# Sheet1.net
KiCad netlist of a schematic drawn in Altium Designer
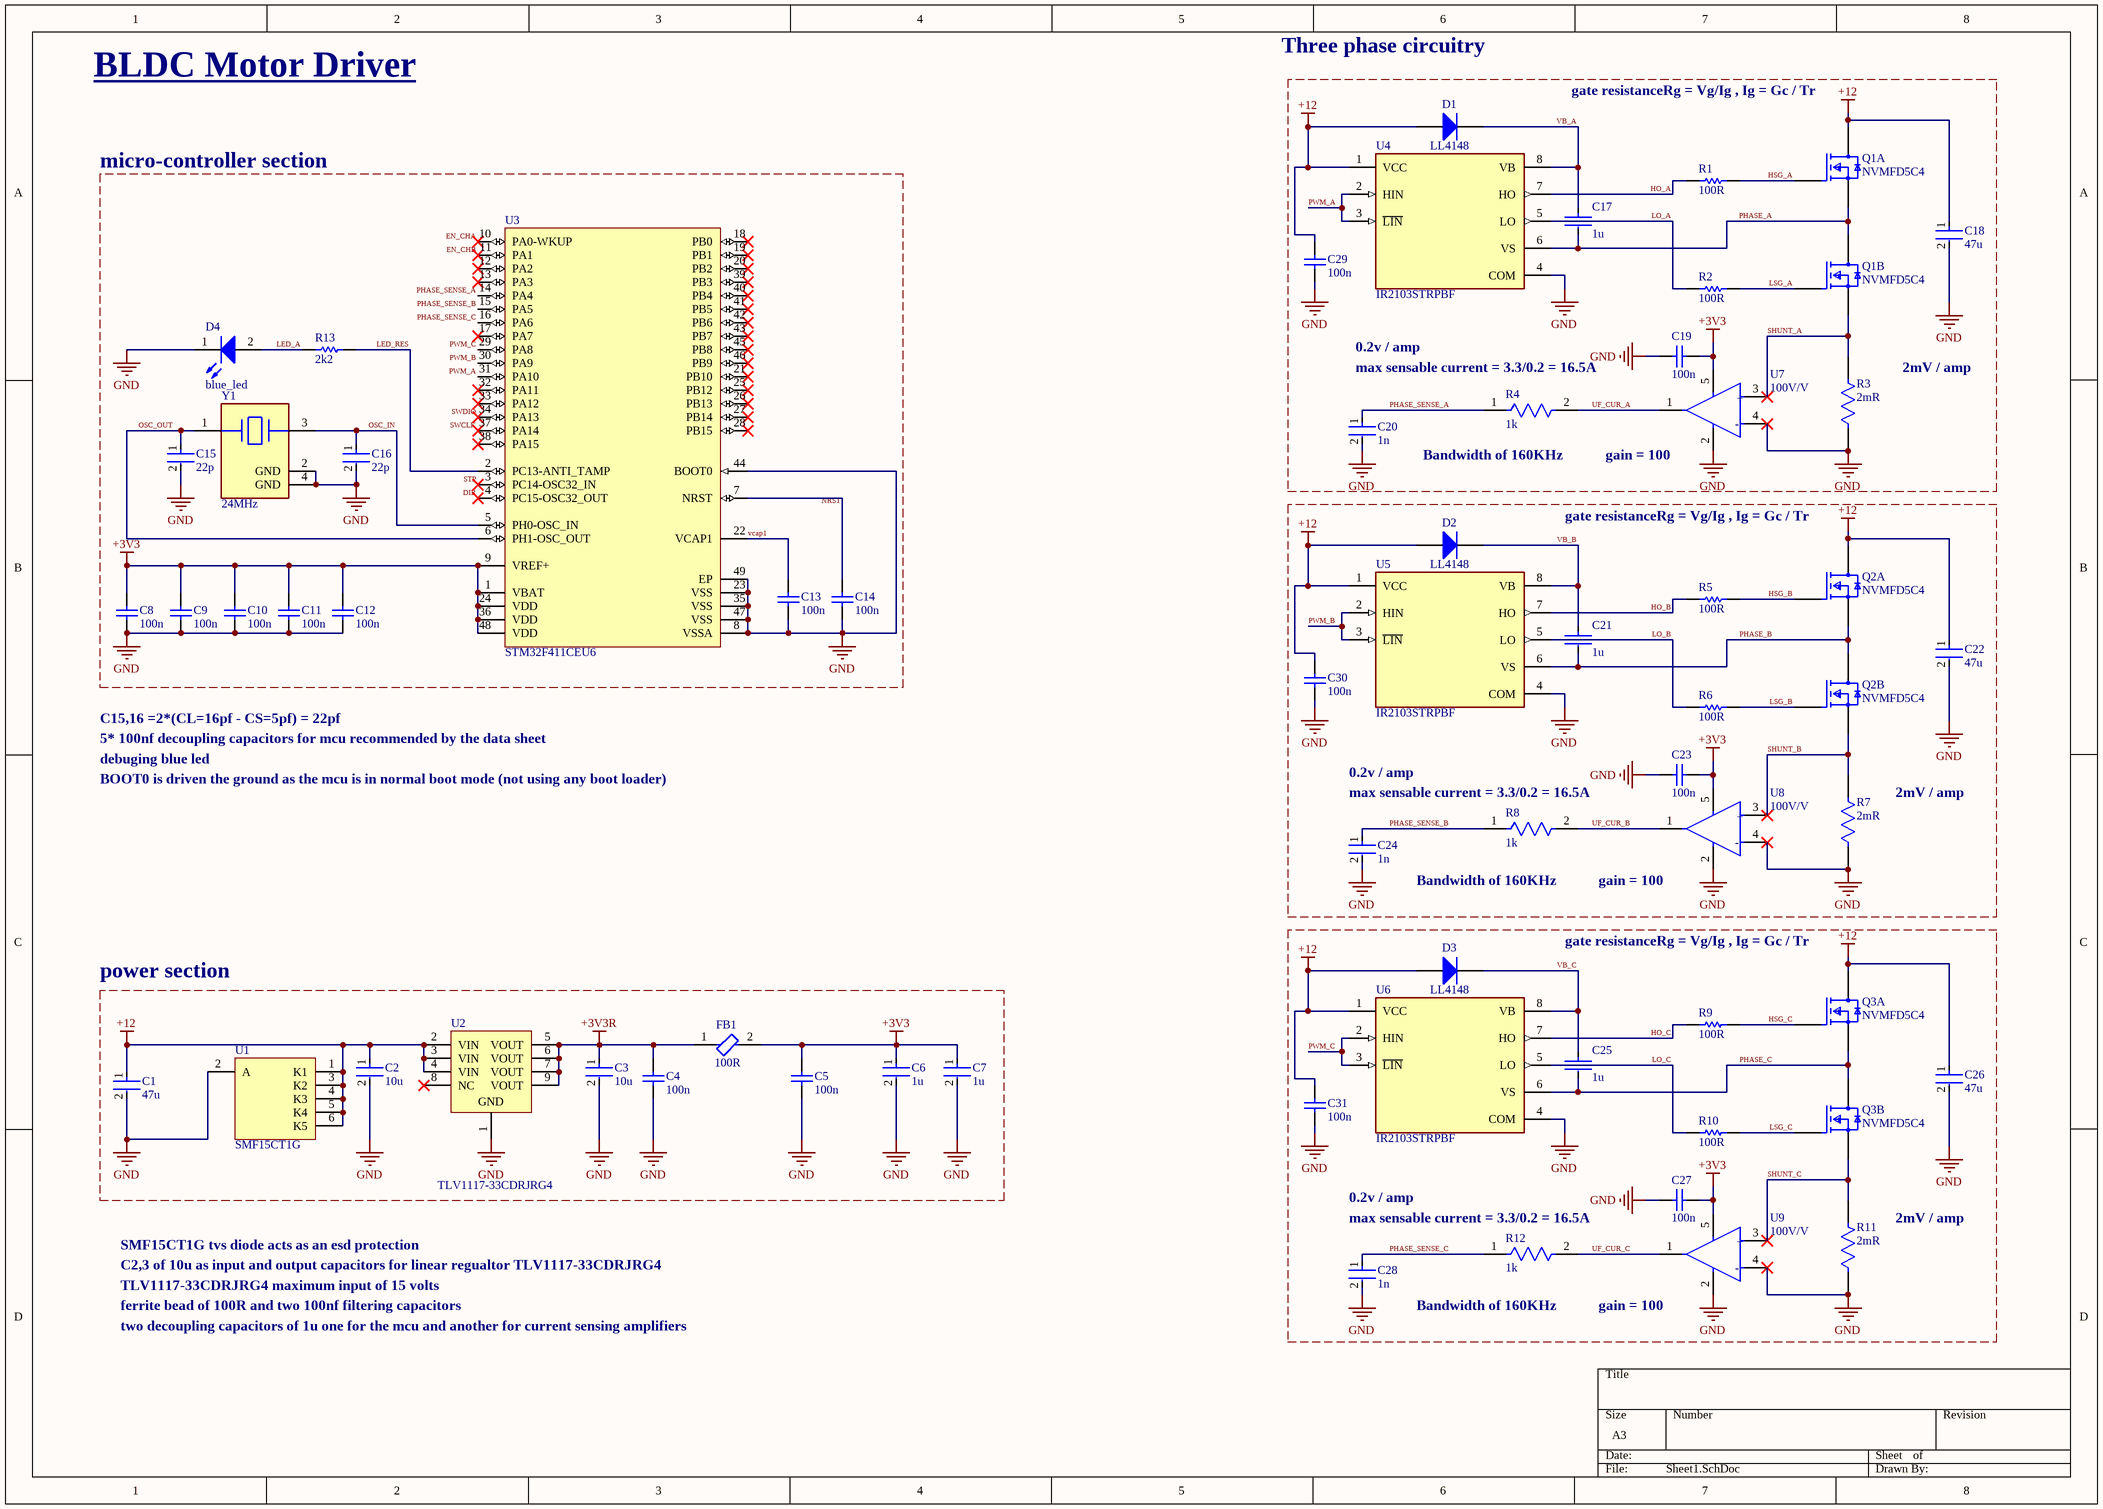
[diagram p0: Sheet1.SchDoc]

(export (version "E")
  (design (tool "Eeschema 10.0.6"))
  (components
    (comp (ref "C1")
      (value "47u")
      (footprint "FP-C3216-160-0_2-MFG")
      (description "Multilayer Ceramic Capacitors 47uF ±20% 25V X5R SMD 1206")
      (fields (field (name "VOLTAGE") "25V") (field (name "TOLERANCE") "20%"))
      (libsource (lib "Altium Content Vault") (part "11868f565c42a9108669ba33697ecf6"))
    )
    (comp (ref "C2")
      (value "10u")
      (footprint "FP-GRM21B-0_1-IPC_C")
      (description "Chip Multilayer Ceramic Capacitors for General Purpose, 0805, 10uF, X5R, 15%, 10%, 16V")
      (fields (field (name "TOLERANCE") "10%") (field (name "VOLTAGE") "16V"))
      (libsource (lib "Altium Content Vault") (part "b4654b650e69147ec39a6b967a45e02"))
    )
    (comp (ref "C3")
      (value "10u")
      (footprint "FP-GRM21B-0_1-IPC_C")
      (description "Chip Multilayer Ceramic Capacitors for General Purpose, 0805, 10uF, X5R, 15%, 10%, 16V")
      (fields (field (name "TOLERANCE") "10%") (field (name "VOLTAGE") "16V"))
      (libsource (lib "Altium Content Vault") (part "b4654b650e69147ec39a6b967a45e02"))
    )
    (comp (ref "C4")
      (value "100n")
      (footprint "CAPC1005X56X25LL10T15")
      (fields
        (field (name "MANUFACTURER") "AVX Interconnect / Elco")
        (field (name "PART NUMBER") "04026D104KAT2A")
      )
      (libsource (lib "Altium Content Vault") (part "CAP"))
    )
    (comp (ref "C5")
      (value "100n")
      (footprint "CAPC1005X56X25LL10T15")
      (fields
        (field (name "MANUFACTURER") "AVX Interconnect / Elco")
        (field (name "PART NUMBER") "04026D104KAT2A")
      )
      (libsource (lib "Altium Content Vault") (part "CAP"))
    )
    (comp (ref "C6")
      (value "1u")
      (footprint "FP-CC0402-MFG")
      (description "CAP CER 1UF 6.3V X5R 0402")
      (fields
        (field (name "MANUFACTURER") "YAGEO")
        (field (name "OCTOPART") "https://octopart.com/cc0402krx5r5bb105-yageo-42244618")
      )
      (libsource (lib "Altium Content Vault") (part "11868f565c42a9108669ba33697ecf6"))
    )
    (comp (ref "C7")
      (value "1u")
      (footprint "FP-CC0402-MFG")
      (description "CAP CER 1UF 6.3V X5R 0402")
      (fields
        (field (name "MANUFACTURER") "YAGEO")
        (field (name "OCTOPART") "https://octopart.com/cc0402krx5r5bb105-yageo-42244618")
      )
      (libsource (lib "Altium Content Vault") (part "11868f565c42a9108669ba33697ecf6"))
    )
    (comp (ref "C8")
      (value "100n")
      (footprint "CAPC1005X56X25LL10T15")
      (fields
        (field (name "MANUFACTURER") "AVX Interconnect / Elco")
        (field (name "PART NUMBER") "04026D104KAT2A")
      )
      (libsource (lib "Altium Content Vault") (part "CAP"))
    )
    (comp (ref "C9")
      (value "100n")
      (footprint "CAPC1005X56X25LL10T15")
      (fields
        (field (name "MANUFACTURER") "AVX Interconnect / Elco")
        (field (name "PART NUMBER") "04026D104KAT2A")
      )
      (libsource (lib "Altium Content Vault") (part "CAP"))
    )
    (comp (ref "C10")
      (value "100n")
      (footprint "CAPC1005X56X25LL10T15")
      (fields
        (field (name "MANUFACTURER") "AVX Interconnect / Elco")
        (field (name "PART NUMBER") "04026D104KAT2A")
      )
      (libsource (lib "Altium Content Vault") (part "CAP"))
    )
    (comp (ref "C11")
      (value "100n")
      (footprint "CAPC1005X56X25LL10T15")
      (fields
        (field (name "MANUFACTURER") "AVX Interconnect / Elco")
        (field (name "PART NUMBER") "04026D104KAT2A")
      )
      (libsource (lib "Altium Content Vault") (part "CAP"))
    )
    (comp (ref "C12")
      (value "100n")
      (footprint "CAPC1005X56X25LL10T15")
      (fields
        (field (name "MANUFACTURER") "AVX Interconnect / Elco")
        (field (name "PART NUMBER") "04026D104KAT2A")
      )
      (libsource (lib "Altium Content Vault") (part "CAP"))
    )
    (comp (ref "C13")
      (value "100n")
      (footprint "CAPC1005X56X25LL10T15")
      (fields
        (field (name "MANUFACTURER") "AVX Interconnect / Elco")
        (field (name "PART NUMBER") "04026D104KAT2A")
      )
      (libsource (lib "Altium Content Vault") (part "CAP"))
    )
    (comp (ref "C14")
      (value "100n")
      (footprint "CAPC1005X56X25LL10T15")
      (fields
        (field (name "MANUFACTURER") "AVX Interconnect / Elco")
        (field (name "PART NUMBER") "04026D104KAT2A")
      )
      (libsource (lib "Altium Content Vault") (part "CAP"))
    )
    (comp (ref "C15")
      (value "22p")
      (footprint "FP-C0402-BB-MFG")
      (description "CAP CER 22PF 16V 5% NP0 0402")
      (fields
        (field (name "TOLERANCE") "0.05")
        (field (name "OCTOPART") "https://octopart.com/c0402c220j4gactu-kemet-9139401")
      )
      (libsource (lib "Altium Content Vault") (part "b4654b650e69147ec39a6b967a45e02"))
    )
    (comp (ref "C16")
      (value "22p")
      (footprint "FP-C0402-BB-MFG")
      (description "CAP CER 22PF 16V 5% NP0 0402")
      (fields
        (field (name "TOLERANCE") "0.05")
        (field (name "OCTOPART") "https://octopart.com/c0402c220j4gactu-kemet-9139401")
      )
      (libsource (lib "Altium Content Vault") (part "b4654b650e69147ec39a6b967a45e02"))
    )
    (comp (ref "C17")
      (value "1u")
      (footprint "FP-CC0402-MFG")
      (description "CAP CER 1UF 6.3V X5R 0402")
      (fields
        (field (name "MANUFACTURER") "YAGEO")
        (field (name "OCTOPART") "https://octopart.com/cc0402krx5r5bb105-yageo-42244618")
      )
      (libsource (lib "") (part "11868f565c42a9108669ba33697ecf6_1"))
    )
    (comp (ref "C18")
      (value "47u")
      (footprint "FP-C3216-160-0_2-MFG")
      (description "Multilayer Ceramic Capacitors 47uF ±20% 25V X5R SMD 1206")
      (fields (field (name "VOLTAGE") "25V") (field (name "TOLERANCE") "20%"))
      (libsource (lib "Altium Content Vault") (part "11868f565c42a9108669ba33697ecf6"))
    )
    (comp (ref "C19")
      (value "100n")
      (footprint "CAPC1005X56X25LL10T15")
      (fields
        (field (name "MANUFACTURER") "AVX Interconnect / Elco")
        (field (name "PART NUMBER") "04026D104KAT2A")
      )
      (libsource (lib "Altium Content Vault") (part "CAP"))
    )
    (comp (ref "C20")
      (value "1n")
      (footprint "FP-GRM155-0_05-IPC_B")
      (description "Chip Multilayer Ceramic Capacitors for General Purpose, 0402, 1000pF, C0G, 30ppm/°C, 5%, 50V")
      (fields (field (name "TOLERANCE") "5%") (field (name "VOLTAGE") "50V"))
      (libsource (lib "Altium Content Vault") (part "02cd4be3c70576c341d710602a673aa"))
    )
    (comp (ref "C21")
      (value "1u")
      (footprint "FP-CC0402-MFG")
      (description "CAP CER 1UF 6.3V X5R 0402")
      (fields
        (field (name "MANUFACTURER") "YAGEO")
        (field (name "OCTOPART") "https://octopart.com/cc0402krx5r5bb105-yageo-42244618")
      )
      (libsource (lib "") (part "11868f565c42a9108669ba33697ecf6_1"))
    )
    (comp (ref "C22")
      (value "47u")
      (footprint "FP-C3216-160-0_2-MFG")
      (description "Multilayer Ceramic Capacitors 47uF ±20% 25V X5R SMD 1206")
      (fields (field (name "VOLTAGE") "25V") (field (name "TOLERANCE") "20%"))
      (libsource (lib "Altium Content Vault") (part "11868f565c42a9108669ba33697ecf6"))
    )
    (comp (ref "C23")
      (value "100n")
      (footprint "CAPC1005X56X25LL10T15")
      (fields
        (field (name "MANUFACTURER") "AVX Interconnect / Elco")
        (field (name "PART NUMBER") "04026D104KAT2A")
      )
      (libsource (lib "Altium Content Vault") (part "CAP"))
    )
    (comp (ref "C24")
      (value "1n")
      (footprint "FP-GRM155-0_05-IPC_B")
      (description "Chip Multilayer Ceramic Capacitors for General Purpose, 0402, 1000pF, C0G, 30ppm/°C, 5%, 50V")
      (fields (field (name "TOLERANCE") "5%") (field (name "VOLTAGE") "50V"))
      (libsource (lib "Altium Content Vault") (part "02cd4be3c70576c341d710602a673aa"))
    )
    (comp (ref "C25")
      (value "1u")
      (footprint "FP-CC0402-MFG")
      (description "CAP CER 1UF 6.3V X5R 0402")
      (fields
        (field (name "MANUFACTURER") "YAGEO")
        (field (name "OCTOPART") "https://octopart.com/cc0402krx5r5bb105-yageo-42244618")
      )
      (libsource (lib "") (part "11868f565c42a9108669ba33697ecf6_1"))
    )
    (comp (ref "C26")
      (value "47u")
      (footprint "FP-C3216-160-0_2-MFG")
      (description "Multilayer Ceramic Capacitors 47uF ±20% 25V X5R SMD 1206")
      (fields (field (name "VOLTAGE") "25V") (field (name "TOLERANCE") "20%"))
      (libsource (lib "Altium Content Vault") (part "11868f565c42a9108669ba33697ecf6"))
    )
    (comp (ref "C27")
      (value "100n")
      (footprint "CAPC1005X56X25LL10T15")
      (fields
        (field (name "MANUFACTURER") "AVX Interconnect / Elco")
        (field (name "PART NUMBER") "04026D104KAT2A")
      )
      (libsource (lib "Altium Content Vault") (part "CAP"))
    )
    (comp (ref "C28")
      (value "1n")
      (footprint "FP-GRM155-0_05-IPC_B")
      (description "Chip Multilayer Ceramic Capacitors for General Purpose, 0402, 1000pF, C0G, 30ppm/°C, 5%, 50V")
      (fields (field (name "TOLERANCE") "5%") (field (name "VOLTAGE") "50V"))
      (libsource (lib "Altium Content Vault") (part "02cd4be3c70576c341d710602a673aa"))
    )
    (comp (ref "C29")
      (value "100n")
      (footprint "CAPC1005X56X25LL10T15")
      (fields
        (field (name "MANUFACTURER") "AVX Interconnect / Elco")
        (field (name "PART NUMBER") "04026D104KAT2A")
      )
      (libsource (lib "Altium Content Vault") (part "CAP"))
    )
    (comp (ref "C30")
      (value "100n")
      (footprint "CAPC1005X56X25LL10T15")
      (fields
        (field (name "MANUFACTURER") "AVX Interconnect / Elco")
        (field (name "PART NUMBER") "04026D104KAT2A")
      )
      (libsource (lib "Altium Content Vault") (part "CAP"))
    )
    (comp (ref "C31")
      (value "100n")
      (footprint "CAPC1005X56X25LL10T15")
      (fields
        (field (name "MANUFACTURER") "AVX Interconnect / Elco")
        (field (name "PART NUMBER") "04026D104KAT2A")
      )
      (libsource (lib "Altium Content Vault") (part "CAP"))
    )
    (comp (ref "D1")
      (value "LL4148")
      (footprint "FAIR-SOD80-2_V")
      (description "Small Signal Diode, 100 V, 0.2 A, -55 to 175 degC, 2-Pin SOD80, RoHS, Tape and Reel")
      (fields (field (name "MANUFACTURER") "Fairchild"))
      (libsource (lib "Altium Content Vault") (part "D-AK-2"))
    )
    (comp (ref "D2")
      (value "LL4148")
      (footprint "FAIR-SOD80-2_V")
      (description "Small Signal Diode, 100 V, 0.2 A, -55 to 175 degC, 2-Pin SOD80, RoHS, Tape and Reel")
      (fields (field (name "MANUFACTURER") "Fairchild"))
      (libsource (lib "Altium Content Vault") (part "D-AK-2"))
    )
    (comp (ref "D3")
      (value "LL4148")
      (footprint "FAIR-SOD80-2_V")
      (description "Small Signal Diode, 100 V, 0.2 A, -55 to 175 degC, 2-Pin SOD80, RoHS, Tape and Reel")
      (fields (field (name "MANUFACTURER") "Fairchild"))
      (libsource (lib "Altium Content Vault") (part "D-AK-2"))
    )
    (comp (ref "D4")
      (value "blue_led")
      (footprint "WL-SMCC_0402_L1W0.5H0.4")
      (description "WL-SMCC SMT Mono-Color Chip LED Compact")
      (libsource (lib "Altium Content Vault") (part "LED_Blue_2A-1K"))
    )
    (comp (ref "FB1")
      (value "100R")
      (footprint "FP-MPZ2012-MFG")
      (fields (field (name "TOLERANCE") "25%"))
      (libsource (lib "Altium Content Vault") (part "5f30dd21d616792df468990f7003faa"))
    )
    (comp (ref "Q1")
      (value "NVMFD5C4")
      (footprint "FP-506BT-MFG")
      (description "NVMFD5C470NLWFT1G Trans MOSFET Array Dual N-CH 40V 11A 8-Pin SOIC-FL T/R")
      (libsource (lib "Altium Content Vault") (part "6438733b1237441ae29c09f3e5635a1"))
    )
    (comp (ref "Q2")
      (value "NVMFD5C4")
      (footprint "FP-506BT-MFG")
      (description "NVMFD5C470NLWFT1G Trans MOSFET Array Dual N-CH 40V 11A 8-Pin SOIC-FL T/R")
      (libsource (lib "Altium Content Vault") (part "6438733b1237441ae29c09f3e5635a1"))
    )
    (comp (ref "Q3")
      (value "NVMFD5C4")
      (footprint "FP-506BT-MFG")
      (description "NVMFD5C470NLWFT1G Trans MOSFET Array Dual N-CH 40V 11A 8-Pin SOIC-FL T/R")
      (libsource (lib "Altium Content Vault") (part "6438733b1237441ae29c09f3e5635a1"))
    )
    (comp (ref "R1")
      (value "100R")
      (footprint "RESC1005X40X25ML05T10")
      (fields (field (name "PART NUMBER") "RC0402FR-07100RL") (field (name "MANUFACTURER") "Yageo / Phycomp"))
      (libsource (lib "Altium Content Vault") (part "RES"))
    )
    (comp (ref "R2")
      (value "100R")
      (footprint "RESC1005X40X25ML05T10")
      (fields (field (name "PART NUMBER") "RC0402FR-07100RL") (field (name "MANUFACTURER") "Yageo / Phycomp"))
      (libsource (lib "Altium Content Vault") (part "RES"))
    )
    (comp (ref "R3")
      (value "2mR")
      (footprint "FP-CSS2H-2512K-2L00F-MFG")
      (fields (field (name "TOLERANCE") "1%"))
      (libsource (lib "Altium Content Vault") (part "1029c3af85768c4190bb7ad29bc67b5"))
    )
    (comp (ref "R4")
      (value "1k")
      (footprint "FP-RC0402-0_4-IPC_A")
      (description "RES 1K OHM 1% 1/16W 0402")
      (fields (field (name "TOLERANCE") "1%"))
      (libsource (lib "") (part "1029c3af85768c4190bb7ad29bc67b5_1"))
    )
    (comp (ref "R5")
      (value "100R")
      (footprint "RESC1005X40X25ML05T10")
      (fields (field (name "PART NUMBER") "RC0402FR-07100RL") (field (name "MANUFACTURER") "Yageo / Phycomp"))
      (libsource (lib "Altium Content Vault") (part "RES"))
    )
    (comp (ref "R6")
      (value "100R")
      (footprint "RESC1005X40X25ML05T10")
      (fields (field (name "PART NUMBER") "RC0402FR-07100RL") (field (name "MANUFACTURER") "Yageo / Phycomp"))
      (libsource (lib "Altium Content Vault") (part "RES"))
    )
    (comp (ref "R7")
      (value "2mR")
      (footprint "FP-CSS2H-2512K-2L00F-MFG")
      (fields (field (name "TOLERANCE") "1%"))
      (libsource (lib "Altium Content Vault") (part "1029c3af85768c4190bb7ad29bc67b5"))
    )
    (comp (ref "R8")
      (value "1k")
      (footprint "FP-RC0402-0_4-IPC_A")
      (description "RES 1K OHM 1% 1/16W 0402")
      (fields (field (name "TOLERANCE") "1%"))
      (libsource (lib "") (part "1029c3af85768c4190bb7ad29bc67b5_1"))
    )
    (comp (ref "R9")
      (value "100R")
      (footprint "RESC1005X40X25ML05T10")
      (fields (field (name "PART NUMBER") "RC0402FR-07100RL") (field (name "MANUFACTURER") "Yageo / Phycomp"))
      (libsource (lib "Altium Content Vault") (part "RES"))
    )
    (comp (ref "R10")
      (value "100R")
      (footprint "RESC1005X40X25ML05T10")
      (fields (field (name "PART NUMBER") "RC0402FR-07100RL") (field (name "MANUFACTURER") "Yageo / Phycomp"))
      (libsource (lib "Altium Content Vault") (part "RES"))
    )
    (comp (ref "R11")
      (value "2mR")
      (footprint "FP-CSS2H-2512K-2L00F-MFG")
      (fields (field (name "TOLERANCE") "1%"))
      (libsource (lib "Altium Content Vault") (part "1029c3af85768c4190bb7ad29bc67b5"))
    )
    (comp (ref "R12")
      (value "1k")
      (footprint "FP-RC0402-0_4-IPC_A")
      (description "RES 1K OHM 1% 1/16W 0402")
      (fields (field (name "TOLERANCE") "1%"))
      (libsource (lib "") (part "1029c3af85768c4190bb7ad29bc67b5_1"))
    )
    (comp (ref "R13")
      (value "2k2")
      (footprint "RESC1005X40X25NL5T10")
      (description "Chip Resistor, 2.2 KOhm, +/- 5%, 0.063 W, -55 to 155 degC, 0402 (1005 Metric), RoHS, Tape and Reel")
      (fields (field (name "TOLERANCE") "5%"))
      (libsource (lib "Altium Content Vault") (part "RES-2"))
    )
    (comp (ref "U1")
      (value "SMF15CT1G")
      (footprint "ONSC-SC70-6-419B-02_W_V")
      (description "5-Line Transient Voltage Suppressor Array, 6-Pin SC70, Pb-Free, Tape and Reel")
      (fields (field (name "MANUFACTURER") "On Semiconductor"))
      (libsource (lib "Altium Content Vault") (part "ONSC-K1A2K3K4K5K6-6"))
    )
    (comp (ref "U2")
      (value "TLV1117-33CDRJRG4")
      (footprint "DRJ8-3000X2200TP")
      (fields (field (name "MANUFACTURER") "Texas Instruments"))
      (libsource (lib "Altium Content Vault") (part "TI-TLV1117-33DRJ8-3000X2200TP"))
    )
    (comp (ref "U3")
      (value "STM32F411CEU6")
      (footprint "STM-UFQFPN48_L")
      (libsource (lib "Altium Content Vault") (part "MC-ARM-STM32F411-UFQFPN48"))
    )
    (comp (ref "U4")
      (value "IR2103STRPBF")
      (footprint "FP-PG-DSO-8-MFG")
      (description "IC GATE DRVR HALF-BRIDGE 8SOIC")
      (libsource (lib "Altium Content Vault") (part "196fa87febc2dffa2411c8510d9fc35"))
    )
    (comp (ref "U5")
      (value "IR2103STRPBF")
      (footprint "FP-PG-DSO-8-MFG")
      (description "IC GATE DRVR HALF-BRIDGE 8SOIC")
      (libsource (lib "Altium Content Vault") (part "196fa87febc2dffa2411c8510d9fc35"))
    )
    (comp (ref "U6")
      (value "IR2103STRPBF")
      (footprint "FP-PG-DSO-8-MFG")
      (description "IC GATE DRVR HALF-BRIDGE 8SOIC")
      (libsource (lib "Altium Content Vault") (part "196fa87febc2dffa2411c8510d9fc35"))
    )
    (comp (ref "U7")
      (value "100V/V")
      (footprint "FP-DBV0005A-IPC_C")
      (description "IC CURR SENSE 1 CIRCUIT SOT23-5")
      (libsource (lib "Altium Content Vault") (part "0a55cf1a948ad01a3239aec1b7efad0"))
    )
    (comp (ref "U8")
      (value "100V/V")
      (footprint "FP-DBV0005A-IPC_C")
      (description "IC CURR SENSE 1 CIRCUIT SOT23-5")
      (libsource (lib "Altium Content Vault") (part "0a55cf1a948ad01a3239aec1b7efad0"))
    )
    (comp (ref "U9")
      (value "100V/V")
      (footprint "FP-DBV0005A-IPC_C")
      (description "IC CURR SENSE 1 CIRCUIT SOT23-5")
      (libsource (lib "Altium Content Vault") (part "0a55cf1a948ad01a3239aec1b7efad0"))
    )
    (comp (ref "Y1")
      (value "24MHz")
      (footprint "FP-ABM3B-MFG")
      (description "Crystal 24MHz ±20ppm 18pF SMD-4 5mm x 3.2mm")
      (fields (field (name "TOLERANCE") "20ppm"))
      (libsource (lib "Altium Content Vault") (part "48e526d86b7f2615d98721063c72f49"))
    )
  )
  (nets
    (net (code "1") (name "+3V3") (class "Default")
      (node (ref "C10") (pin "2") (pinfunction "2_2") (pintype "passive"))
      (node (ref "C11") (pin "2") (pinfunction "2_2") (pintype "passive"))
      (node (ref "C12") (pin "2") (pinfunction "2_2") (pintype "passive"))
      (node (ref "C19") (pin "1") (pinfunction "1_1") (pintype "passive"))
      (node (ref "C23") (pin "1") (pinfunction "1_1") (pintype "passive"))
      (node (ref "C27") (pin "1") (pinfunction "1_1") (pintype "passive"))
      (node (ref "C5") (pin "2") (pinfunction "2_2") (pintype "passive"))
      (node (ref "C6") (pin "1") (pinfunction "1_1") (pintype "passive"))
      (node (ref "C7") (pin "1") (pinfunction "1_1") (pintype "passive"))
      (node (ref "C8") (pin "2") (pinfunction "2_2") (pintype "passive"))
      (node (ref "C9") (pin "2") (pinfunction "2_2") (pintype "passive"))
      (node (ref "FB1") (pin "2") (pinfunction "2_2") (pintype "passive"))
      (node (ref "U3") (pin "1") (pinfunction "VBAT_1") (pintype "power_in"))
      (node (ref "U3") (pin "24") (pinfunction "VDD_24") (pintype "power_in"))
      (node (ref "U3") (pin "36") (pinfunction "VDD_36") (pintype "power_in"))
      (node (ref "U3") (pin "48") (pinfunction "VDD_48") (pintype "power_in"))
      (node (ref "U3") (pin "9") (pinfunction "VREF+_9") (pintype "power_in"))
      (node (ref "U7") (pin "5") (pinfunction "VS_5") (pintype "power_in"))
      (node (ref "U8") (pin "5") (pinfunction "VS_5") (pintype "power_in"))
      (node (ref "U9") (pin "5") (pinfunction "VS_5") (pintype "power_in"))
    )
    (net (code "2") (name "+3V3R") (class "Default")
      (node (ref "C3") (pin "1") (pinfunction "1_1") (pintype "passive"))
      (node (ref "C4") (pin "2") (pinfunction "2_2") (pintype "passive"))
      (node (ref "FB1") (pin "1") (pinfunction "1_1") (pintype "passive"))
      (node (ref "U2") (pin "5") (pinfunction "VOUT_5") (pintype "power_in"))
      (node (ref "U2") (pin "6") (pinfunction "VOUT_6") (pintype "power_in"))
      (node (ref "U2") (pin "7") (pinfunction "VOUT_7") (pintype "power_in"))
      (node (ref "U2") (pin "9") (pinfunction "VOUT_9") (pintype "power_in"))
    )
    (net (code "3") (name "+12") (class "Default")
      (node (ref "C1") (pin "1") (pinfunction "1_1") (pintype "passive"))
      (node (ref "C18") (pin "1") (pinfunction "1_1") (pintype "passive"))
      (node (ref "C2") (pin "1") (pinfunction "1_1") (pintype "passive"))
      (node (ref "C22") (pin "1") (pinfunction "1_1") (pintype "passive"))
      (node (ref "C26") (pin "1") (pinfunction "1_1") (pintype "passive"))
      (node (ref "C29") (pin "2") (pinfunction "2_2") (pintype "passive"))
      (node (ref "C30") (pin "2") (pinfunction "2_2") (pintype "passive"))
      (node (ref "C31") (pin "2") (pinfunction "2_2") (pintype "passive"))
      (node (ref "D1") (pin "1") (pinfunction "A_1") (pintype "passive"))
      (node (ref "D2") (pin "1") (pinfunction "A_1") (pintype "passive"))
      (node (ref "D3") (pin "1") (pinfunction "A_1") (pintype "passive"))
      (node (ref "Q1") (pin "7-8") (pinfunction "D1_7-8") (pintype "passive"))
      (node (ref "Q2") (pin "7-8") (pinfunction "D1_7-8") (pintype "passive"))
      (node (ref "Q3") (pin "7-8") (pinfunction "D1_7-8") (pintype "passive"))
      (node (ref "U1") (pin "1") (pinfunction "K1_1") (pintype "passive"))
      (node (ref "U1") (pin "3") (pinfunction "K2_3") (pintype "passive"))
      (node (ref "U1") (pin "4") (pinfunction "K3_4") (pintype "passive"))
      (node (ref "U1") (pin "5") (pinfunction "K4_5") (pintype "passive"))
      (node (ref "U1") (pin "6") (pinfunction "K5_6") (pintype "passive"))
      (node (ref "U2") (pin "2") (pinfunction "VIN_2") (pintype "power_in"))
      (node (ref "U2") (pin "3") (pinfunction "VIN_3") (pintype "power_in"))
      (node (ref "U2") (pin "4") (pinfunction "VIN_4") (pintype "power_in"))
      (node (ref "U4") (pin "1") (pinfunction "VCC_1") (pintype "power_in"))
      (node (ref "U5") (pin "1") (pinfunction "VCC_1") (pintype "power_in"))
      (node (ref "U6") (pin "1") (pinfunction "VCC_1") (pintype "power_in"))
    )
    (net (code "4") (name "/DIR") (class "Default")
      (node (ref "U3") (pin "4") (pinfunction "PC15-OSC32_OUT_4") (pintype "bidirectional+no_connect"))
    )
    (net (code "5") (name "/EN_CHA") (class "Default")
      (node (ref "U3") (pin "10") (pinfunction "PA0-WKUP_10") (pintype "bidirectional+no_connect"))
    )
    (net (code "6") (name "/EN_CHB") (class "Default")
      (node (ref "U3") (pin "11") (pinfunction "PA1_11") (pintype "bidirectional+no_connect"))
    )
    (net (code "7") (name "/HO_A") (class "Default")
      (node (ref "R1") (pin "1") (pinfunction "1_1") (pintype "passive"))
      (node (ref "U4") (pin "7") (pinfunction "HO_7") (pintype "output"))
    )
    (net (code "8") (name "/HO_B") (class "Default")
      (node (ref "R5") (pin "1") (pinfunction "1_1") (pintype "passive"))
      (node (ref "U5") (pin "7") (pinfunction "HO_7") (pintype "output"))
    )
    (net (code "9") (name "/HO_C") (class "Default")
      (node (ref "R9") (pin "1") (pinfunction "1_1") (pintype "passive"))
      (node (ref "U6") (pin "7") (pinfunction "HO_7") (pintype "output"))
    )
    (net (code "10") (name "/HSG_A") (class "Default")
      (node (ref "Q1") (pin "2") (pinfunction "G1_2") (pintype "passive"))
      (node (ref "R1") (pin "2") (pinfunction "2_2") (pintype "passive"))
    )
    (net (code "11") (name "/HSG_B") (class "Default")
      (node (ref "Q2") (pin "2") (pinfunction "G1_2") (pintype "passive"))
      (node (ref "R5") (pin "2") (pinfunction "2_2") (pintype "passive"))
    )
    (net (code "12") (name "/HSG_C") (class "Default")
      (node (ref "Q3") (pin "2") (pinfunction "G1_2") (pintype "passive"))
      (node (ref "R9") (pin "2") (pinfunction "2_2") (pintype "passive"))
    )
    (net (code "13") (name "/LED_A") (class "Default")
      (node (ref "D4") (pin "2") (pinfunction "A_2") (pintype "passive"))
      (node (ref "R13") (pin "1") (pinfunction "1_1") (pintype "passive"))
    )
    (net (code "14") (name "/LED_RES") (class "Default")
      (node (ref "R13") (pin "2") (pinfunction "2_2") (pintype "passive"))
      (node (ref "U3") (pin "2") (pinfunction "PC13-ANTI_TAMP_2") (pintype "bidirectional"))
    )
    (net (code "15") (name "/LO_A") (class "Default")
      (node (ref "R2") (pin "1") (pinfunction "1_1") (pintype "passive"))
      (node (ref "U4") (pin "5") (pinfunction "LO_5") (pintype "output"))
    )
    (net (code "16") (name "/LO_B") (class "Default")
      (node (ref "R6") (pin "1") (pinfunction "1_1") (pintype "passive"))
      (node (ref "U5") (pin "5") (pinfunction "LO_5") (pintype "output"))
    )
    (net (code "17") (name "/LO_C") (class "Default")
      (node (ref "R10") (pin "1") (pinfunction "1_1") (pintype "passive"))
      (node (ref "U6") (pin "5") (pinfunction "LO_5") (pintype "output"))
    )
    (net (code "18") (name "/LSG_A") (class "Default")
      (node (ref "Q1") (pin "4") (pinfunction "G2_4") (pintype "passive"))
      (node (ref "R2") (pin "2") (pinfunction "2_2") (pintype "passive"))
    )
    (net (code "19") (name "/LSG_B") (class "Default")
      (node (ref "Q2") (pin "4") (pinfunction "G2_4") (pintype "passive"))
      (node (ref "R6") (pin "2") (pinfunction "2_2") (pintype "passive"))
    )
    (net (code "20") (name "/LSG_C") (class "Default")
      (node (ref "Q3") (pin "4") (pinfunction "G2_4") (pintype "passive"))
      (node (ref "R10") (pin "2") (pinfunction "2_2") (pintype "passive"))
    )
    (net (code "21") (name "/NRST") (class "Default")
      (node (ref "C14") (pin "2") (pinfunction "2_2") (pintype "passive"))
      (node (ref "U3") (pin "7") (pinfunction "NRST_7") (pintype "bidirectional"))
    )
    (net (code "22") (name "/OSC_IN") (class "Default")
      (node (ref "C16") (pin "1") (pinfunction "1_1") (pintype "passive"))
      (node (ref "U3") (pin "5") (pinfunction "PH0-OSC_IN_5") (pintype "bidirectional"))
      (node (ref "Y1") (pin "3") (pinfunction "3_3") (pintype "passive"))
    )
    (net (code "23") (name "/OSC_OUT") (class "Default")
      (node (ref "C15") (pin "1") (pinfunction "1_1") (pintype "passive"))
      (node (ref "U3") (pin "6") (pinfunction "PH1-OSC_OUT_6") (pintype "bidirectional"))
      (node (ref "Y1") (pin "1") (pinfunction "1_1") (pintype "passive"))
    )
    (net (code "24") (name "/PHASE_A") (class "Default")
      (node (ref "C17") (pin "2") (pinfunction "2_2") (pintype "passive"))
      (node (ref "Q1") (pin "1") (pinfunction "S1_1") (pintype "passive"))
      (node (ref "Q1") (pin "5-6") (pinfunction "D2_5-6") (pintype "passive"))
      (node (ref "U4") (pin "6") (pinfunction "VS_6") (pintype "power_in"))
    )
    (net (code "25") (name "/PHASE_B") (class "Default")
      (node (ref "C21") (pin "2") (pinfunction "2_2") (pintype "passive"))
      (node (ref "Q2") (pin "1") (pinfunction "S1_1") (pintype "passive"))
      (node (ref "Q2") (pin "5-6") (pinfunction "D2_5-6") (pintype "passive"))
      (node (ref "U5") (pin "6") (pinfunction "VS_6") (pintype "power_in"))
    )
    (net (code "26") (name "/PHASE_C") (class "Default")
      (node (ref "C25") (pin "2") (pinfunction "2_2") (pintype "passive"))
      (node (ref "Q3") (pin "1") (pinfunction "S1_1") (pintype "passive"))
      (node (ref "Q3") (pin "5-6") (pinfunction "D2_5-6") (pintype "passive"))
      (node (ref "U6") (pin "6") (pinfunction "VS_6") (pintype "power_in"))
    )
    (net (code "27") (name "/PHASE_SENSE_A") (class "Default")
      (node (ref "C20") (pin "1") (pinfunction "1_1") (pintype "passive"))
      (node (ref "R4") (pin "1") (pinfunction "1_1") (pintype "passive"))
      (node (ref "U3") (pin "14") (pinfunction "PA4_14") (pintype "bidirectional"))
    )
    (net (code "28") (name "/PHASE_SENSE_B") (class "Default")
      (node (ref "C24") (pin "1") (pinfunction "1_1") (pintype "passive"))
      (node (ref "R8") (pin "1") (pinfunction "1_1") (pintype "passive"))
      (node (ref "U3") (pin "15") (pinfunction "PA5_15") (pintype "bidirectional"))
    )
    (net (code "29") (name "/PHASE_SENSE_C") (class "Default")
      (node (ref "C28") (pin "1") (pinfunction "1_1") (pintype "passive"))
      (node (ref "R12") (pin "1") (pinfunction "1_1") (pintype "passive"))
      (node (ref "U3") (pin "16") (pinfunction "PA6_16") (pintype "bidirectional"))
    )
    (net (code "30") (name "/PWM_A") (class "Default")
      (node (ref "U3") (pin "31") (pinfunction "PA10_31") (pintype "bidirectional"))
      (node (ref "U4") (pin "2") (pinfunction "HIN_2") (pintype "input"))
      (node (ref "U4") (pin "3") (pinfunction "~{LIN}_3") (pintype "input"))
    )
    (net (code "31") (name "/PWM_B") (class "Default")
      (node (ref "U3") (pin "30") (pinfunction "PA9_30") (pintype "bidirectional"))
      (node (ref "U5") (pin "2") (pinfunction "HIN_2") (pintype "input"))
      (node (ref "U5") (pin "3") (pinfunction "~{LIN}_3") (pintype "input"))
    )
    (net (code "32") (name "/PWM_C") (class "Default")
      (node (ref "U3") (pin "29") (pinfunction "PA8_29") (pintype "bidirectional"))
      (node (ref "U6") (pin "2") (pinfunction "HIN_2") (pintype "input"))
      (node (ref "U6") (pin "3") (pinfunction "~{LIN}_3") (pintype "input"))
    )
    (net (code "33") (name "/SHUNT_A") (class "Default")
      (node (ref "Q1") (pin "3") (pinfunction "S2_3") (pintype "passive"))
      (node (ref "R3") (pin "2") (pinfunction "2_2") (pintype "passive"))
      (node (ref "U7") (pin "3") (pinfunction "IN+_3") (pintype "tri_state"))
    )
    (net (code "34") (name "/SHUNT_B") (class "Default")
      (node (ref "Q2") (pin "3") (pinfunction "S2_3") (pintype "passive"))
      (node (ref "R7") (pin "2") (pinfunction "2_2") (pintype "passive"))
      (node (ref "U8") (pin "3") (pinfunction "IN+_3") (pintype "tri_state"))
    )
    (net (code "35") (name "/SHUNT_C") (class "Default")
      (node (ref "Q3") (pin "3") (pinfunction "S2_3") (pintype "passive"))
      (node (ref "R11") (pin "2") (pinfunction "2_2") (pintype "passive"))
      (node (ref "U9") (pin "3") (pinfunction "IN+_3") (pintype "tri_state"))
    )
    (net (code "36") (name "/STP") (class "Default")
      (node (ref "U3") (pin "3") (pinfunction "PC14-OSC32_IN_3") (pintype "bidirectional+no_connect"))
    )
    (net (code "37") (name "/SWCLK") (class "Default")
      (node (ref "U3") (pin "37") (pinfunction "PA14_37") (pintype "bidirectional+no_connect"))
    )
    (net (code "38") (name "/SWDIO") (class "Default")
      (node (ref "U3") (pin "34") (pinfunction "PA13_34") (pintype "bidirectional+no_connect"))
    )
    (net (code "39") (name "/UF_CUR_A") (class "Default")
      (node (ref "R4") (pin "2") (pinfunction "2_2") (pintype "passive"))
      (node (ref "U7") (pin "1") (pinfunction "OUT_1") (pintype "power_in"))
    )
    (net (code "40") (name "/UF_CUR_B") (class "Default")
      (node (ref "R8") (pin "2") (pinfunction "2_2") (pintype "passive"))
      (node (ref "U8") (pin "1") (pinfunction "OUT_1") (pintype "power_in"))
    )
    (net (code "41") (name "/UF_CUR_C") (class "Default")
      (node (ref "R12") (pin "2") (pinfunction "2_2") (pintype "passive"))
      (node (ref "U9") (pin "1") (pinfunction "OUT_1") (pintype "power_in"))
    )
    (net (code "42") (name "/VB_A") (class "Default")
      (node (ref "C17") (pin "1") (pinfunction "1_1") (pintype "passive"))
      (node (ref "D1") (pin "2") (pinfunction "K_2") (pintype "passive"))
      (node (ref "U4") (pin "8") (pinfunction "VB_8") (pintype "power_in"))
    )
    (net (code "43") (name "/VB_B") (class "Default")
      (node (ref "C21") (pin "1") (pinfunction "1_1") (pintype "passive"))
      (node (ref "D2") (pin "2") (pinfunction "K_2") (pintype "passive"))
      (node (ref "U5") (pin "8") (pinfunction "VB_8") (pintype "power_in"))
    )
    (net (code "44") (name "/VB_C") (class "Default")
      (node (ref "C25") (pin "1") (pinfunction "1_1") (pintype "passive"))
      (node (ref "D3") (pin "2") (pinfunction "K_2") (pintype "passive"))
      (node (ref "U6") (pin "8") (pinfunction "VB_8") (pintype "power_in"))
    )
    (net (code "45") (name "/vcap1") (class "Default")
      (node (ref "C13") (pin "2") (pinfunction "2_2") (pintype "passive"))
      (node (ref "U3") (pin "22") (pinfunction "VCAP1_22") (pintype "passive"))
    )
    (net (code "46") (name "GND") (class "Default")
      (node (ref "C1") (pin "2") (pinfunction "2_2") (pintype "passive"))
      (node (ref "C10") (pin "1") (pinfunction "1_1") (pintype "passive"))
      (node (ref "C11") (pin "1") (pinfunction "1_1") (pintype "passive"))
      (node (ref "C12") (pin "1") (pinfunction "1_1") (pintype "passive"))
      (node (ref "C13") (pin "1") (pinfunction "1_1") (pintype "passive"))
      (node (ref "C14") (pin "1") (pinfunction "1_1") (pintype "passive"))
      (node (ref "C15") (pin "2") (pinfunction "2_2") (pintype "passive"))
      (node (ref "C16") (pin "2") (pinfunction "2_2") (pintype "passive"))
      (node (ref "C18") (pin "2") (pinfunction "2_2") (pintype "passive"))
      (node (ref "C19") (pin "2") (pinfunction "2_2") (pintype "passive"))
      (node (ref "C2") (pin "2") (pinfunction "2_2") (pintype "passive"))
      (node (ref "C20") (pin "2") (pinfunction "2_2") (pintype "passive"))
      (node (ref "C22") (pin "2") (pinfunction "2_2") (pintype "passive"))
      (node (ref "C23") (pin "2") (pinfunction "2_2") (pintype "passive"))
      (node (ref "C24") (pin "2") (pinfunction "2_2") (pintype "passive"))
      (node (ref "C26") (pin "2") (pinfunction "2_2") (pintype "passive"))
      (node (ref "C27") (pin "2") (pinfunction "2_2") (pintype "passive"))
      (node (ref "C28") (pin "2") (pinfunction "2_2") (pintype "passive"))
      (node (ref "C29") (pin "1") (pinfunction "1_1") (pintype "passive"))
      (node (ref "C3") (pin "2") (pinfunction "2_2") (pintype "passive"))
      (node (ref "C30") (pin "1") (pinfunction "1_1") (pintype "passive"))
      (node (ref "C31") (pin "1") (pinfunction "1_1") (pintype "passive"))
      (node (ref "C4") (pin "1") (pinfunction "1_1") (pintype "passive"))
      (node (ref "C5") (pin "1") (pinfunction "1_1") (pintype "passive"))
      (node (ref "C6") (pin "2") (pinfunction "2_2") (pintype "passive"))
      (node (ref "C7") (pin "2") (pinfunction "2_2") (pintype "passive"))
      (node (ref "C8") (pin "1") (pinfunction "1_1") (pintype "passive"))
      (node (ref "C9") (pin "1") (pinfunction "1_1") (pintype "passive"))
      (node (ref "D4") (pin "1") (pinfunction "K_1") (pintype "passive"))
      (node (ref "R11") (pin "1") (pinfunction "1_1") (pintype "passive"))
      (node (ref "R3") (pin "1") (pinfunction "1_1") (pintype "passive"))
      (node (ref "R7") (pin "1") (pinfunction "1_1") (pintype "passive"))
      (node (ref "U1") (pin "2") (pinfunction "A_2") (pintype "passive"))
      (node (ref "U2") (pin "1") (pinfunction "GND_1") (pintype "power_in"))
      (node (ref "U3") (pin "23") (pinfunction "VSS_23") (pintype "power_in"))
      (node (ref "U3") (pin "35") (pinfunction "VSS_35") (pintype "power_in"))
      (node (ref "U3") (pin "44") (pinfunction "BOOT0_44") (pintype "input"))
      (node (ref "U3") (pin "47") (pinfunction "VSS_47") (pintype "power_in"))
      (node (ref "U3") (pin "49") (pinfunction "EP_49") (pintype "power_in"))
      (node (ref "U3") (pin "8") (pinfunction "VSSA_8") (pintype "power_in"))
      (node (ref "U4") (pin "4") (pinfunction "COM_4") (pintype "passive"))
      (node (ref "U5") (pin "4") (pinfunction "COM_4") (pintype "passive"))
      (node (ref "U6") (pin "4") (pinfunction "COM_4") (pintype "passive"))
      (node (ref "U7") (pin "2") (pinfunction "GND_2") (pintype "power_in"))
      (node (ref "U7") (pin "4") (pinfunction "IN-_4") (pintype "tri_state"))
      (node (ref "U8") (pin "2") (pinfunction "GND_2") (pintype "power_in"))
      (node (ref "U8") (pin "4") (pinfunction "IN-_4") (pintype "tri_state"))
      (node (ref "U9") (pin "2") (pinfunction "GND_2") (pintype "power_in"))
      (node (ref "U9") (pin "4") (pinfunction "IN-_4") (pintype "tri_state"))
      (node (ref "Y1") (pin "2") (pinfunction "GND_2") (pintype "power_in"))
      (node (ref "Y1") (pin "4") (pinfunction "GND_4") (pintype "power_in"))
    )
    (net (code "47") (name "unconnected-(U2-NC-Pad8)") (class "Default")
      (node (ref "U2") (pin "8") (pinfunction "NC_8") (pintype "passive+no_connect"))
    )
    (net (code "48") (name "unconnected-(U3-PA2-Pad12)") (class "Default")
      (node (ref "U3") (pin "12") (pinfunction "PA2_12") (pintype "bidirectional+no_connect"))
    )
    (net (code "49") (name "unconnected-(U3-PA3-Pad13)") (class "Default")
      (node (ref "U3") (pin "13") (pinfunction "PA3_13") (pintype "bidirectional+no_connect"))
    )
    (net (code "50") (name "unconnected-(U3-PA7-Pad17)") (class "Default")
      (node (ref "U3") (pin "17") (pinfunction "PA7_17") (pintype "bidirectional+no_connect"))
    )
    (net (code "51") (name "unconnected-(U3-PA11-Pad32)") (class "Default")
      (node (ref "U3") (pin "32") (pinfunction "PA11_32") (pintype "bidirectional+no_connect"))
    )
    (net (code "52") (name "unconnected-(U3-PA12-Pad33)") (class "Default")
      (node (ref "U3") (pin "33") (pinfunction "PA12_33") (pintype "bidirectional+no_connect"))
    )
    (net (code "53") (name "unconnected-(U3-PA15-Pad38)") (class "Default")
      (node (ref "U3") (pin "38") (pinfunction "PA15_38") (pintype "bidirectional+no_connect"))
    )
    (net (code "54") (name "unconnected-(U3-PB0-Pad18)") (class "Default")
      (node (ref "U3") (pin "18") (pinfunction "PB0_18") (pintype "bidirectional+no_connect"))
    )
    (net (code "55") (name "unconnected-(U3-PB1-Pad19)") (class "Default")
      (node (ref "U3") (pin "19") (pinfunction "PB1_19") (pintype "bidirectional+no_connect"))
    )
    (net (code "56") (name "unconnected-(U3-PB2-Pad20)") (class "Default")
      (node (ref "U3") (pin "20") (pinfunction "PB2_20") (pintype "bidirectional+no_connect"))
    )
    (net (code "57") (name "unconnected-(U3-PB3-Pad39)") (class "Default")
      (node (ref "U3") (pin "39") (pinfunction "PB3_39") (pintype "bidirectional+no_connect"))
    )
    (net (code "58") (name "unconnected-(U3-PB4-Pad40)") (class "Default")
      (node (ref "U3") (pin "40") (pinfunction "PB4_40") (pintype "bidirectional+no_connect"))
    )
    (net (code "59") (name "unconnected-(U3-PB5-Pad41)") (class "Default")
      (node (ref "U3") (pin "41") (pinfunction "PB5_41") (pintype "bidirectional+no_connect"))
    )
    (net (code "60") (name "unconnected-(U3-PB6-Pad42)") (class "Default")
      (node (ref "U3") (pin "42") (pinfunction "PB6_42") (pintype "bidirectional+no_connect"))
    )
    (net (code "61") (name "unconnected-(U3-PB7-Pad43)") (class "Default")
      (node (ref "U3") (pin "43") (pinfunction "PB7_43") (pintype "bidirectional+no_connect"))
    )
    (net (code "62") (name "unconnected-(U3-PB8-Pad45)") (class "Default")
      (node (ref "U3") (pin "45") (pinfunction "PB8_45") (pintype "bidirectional+no_connect"))
    )
    (net (code "63") (name "unconnected-(U3-PB9-Pad46)") (class "Default")
      (node (ref "U3") (pin "46") (pinfunction "PB9_46") (pintype "bidirectional+no_connect"))
    )
    (net (code "64") (name "unconnected-(U3-PB10-Pad21)") (class "Default")
      (node (ref "U3") (pin "21") (pinfunction "PB10_21") (pintype "bidirectional+no_connect"))
    )
    (net (code "65") (name "unconnected-(U3-PB12-Pad25)") (class "Default")
      (node (ref "U3") (pin "25") (pinfunction "PB12_25") (pintype "bidirectional+no_connect"))
    )
    (net (code "66") (name "unconnected-(U3-PB13-Pad26)") (class "Default")
      (node (ref "U3") (pin "26") (pinfunction "PB13_26") (pintype "bidirectional+no_connect"))
    )
    (net (code "67") (name "unconnected-(U3-PB14-Pad27)") (class "Default")
      (node (ref "U3") (pin "27") (pinfunction "PB14_27") (pintype "bidirectional+no_connect"))
    )
    (net (code "68") (name "unconnected-(U3-PB15-Pad28)") (class "Default")
      (node (ref "U3") (pin "28") (pinfunction "PB15_28") (pintype "bidirectional+no_connect"))
    )
  )
)
